# M-S_rev_01.net
KiCad netlist of a schematic drawn in EAGLE
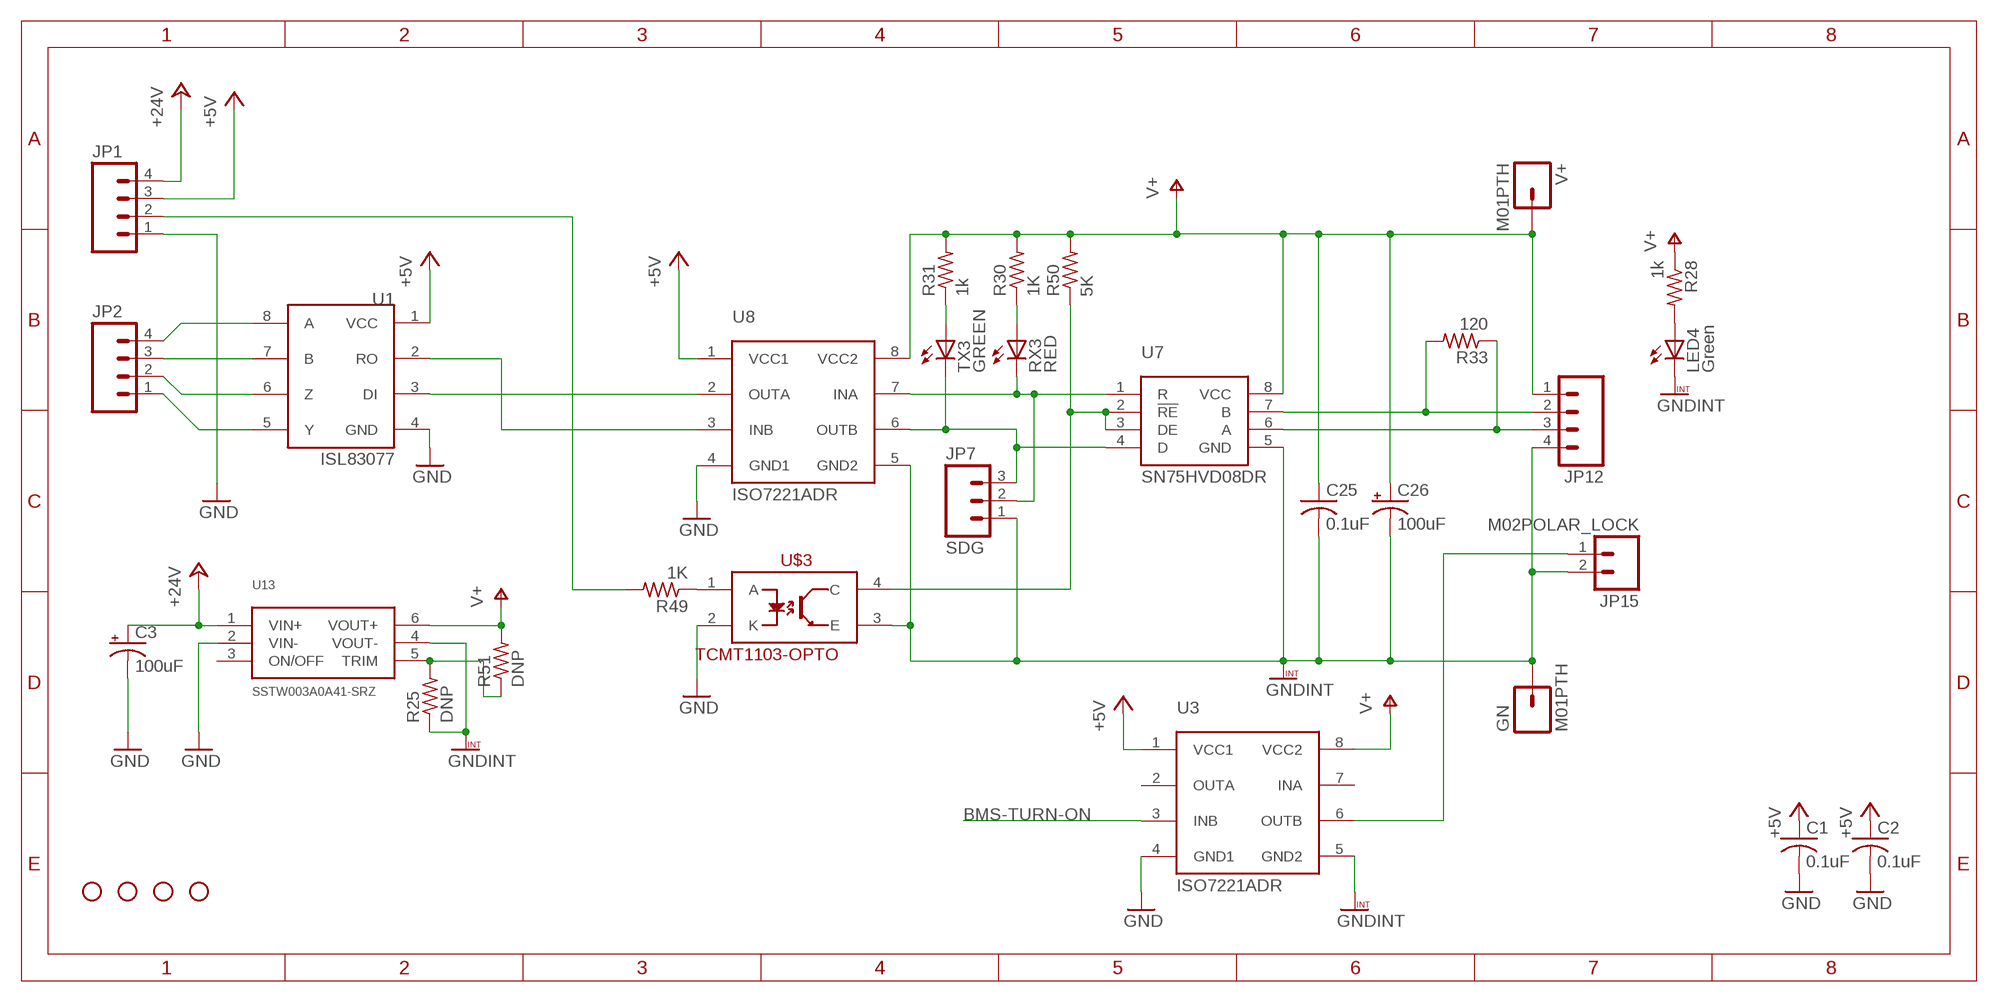
[diagram p0: schematic, sheet 1]
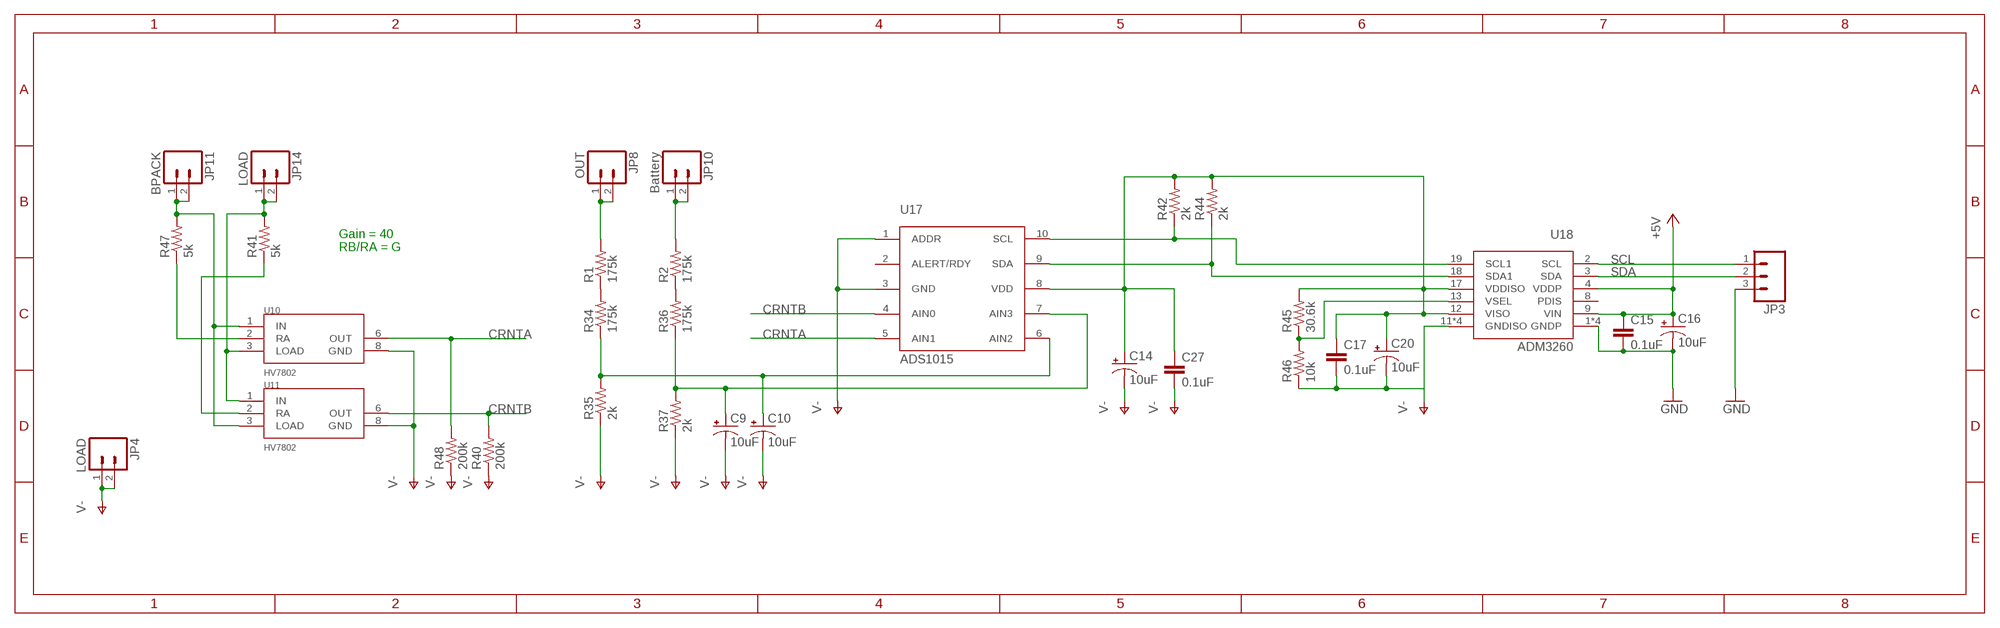
[diagram p1: schematic, sheet 2]
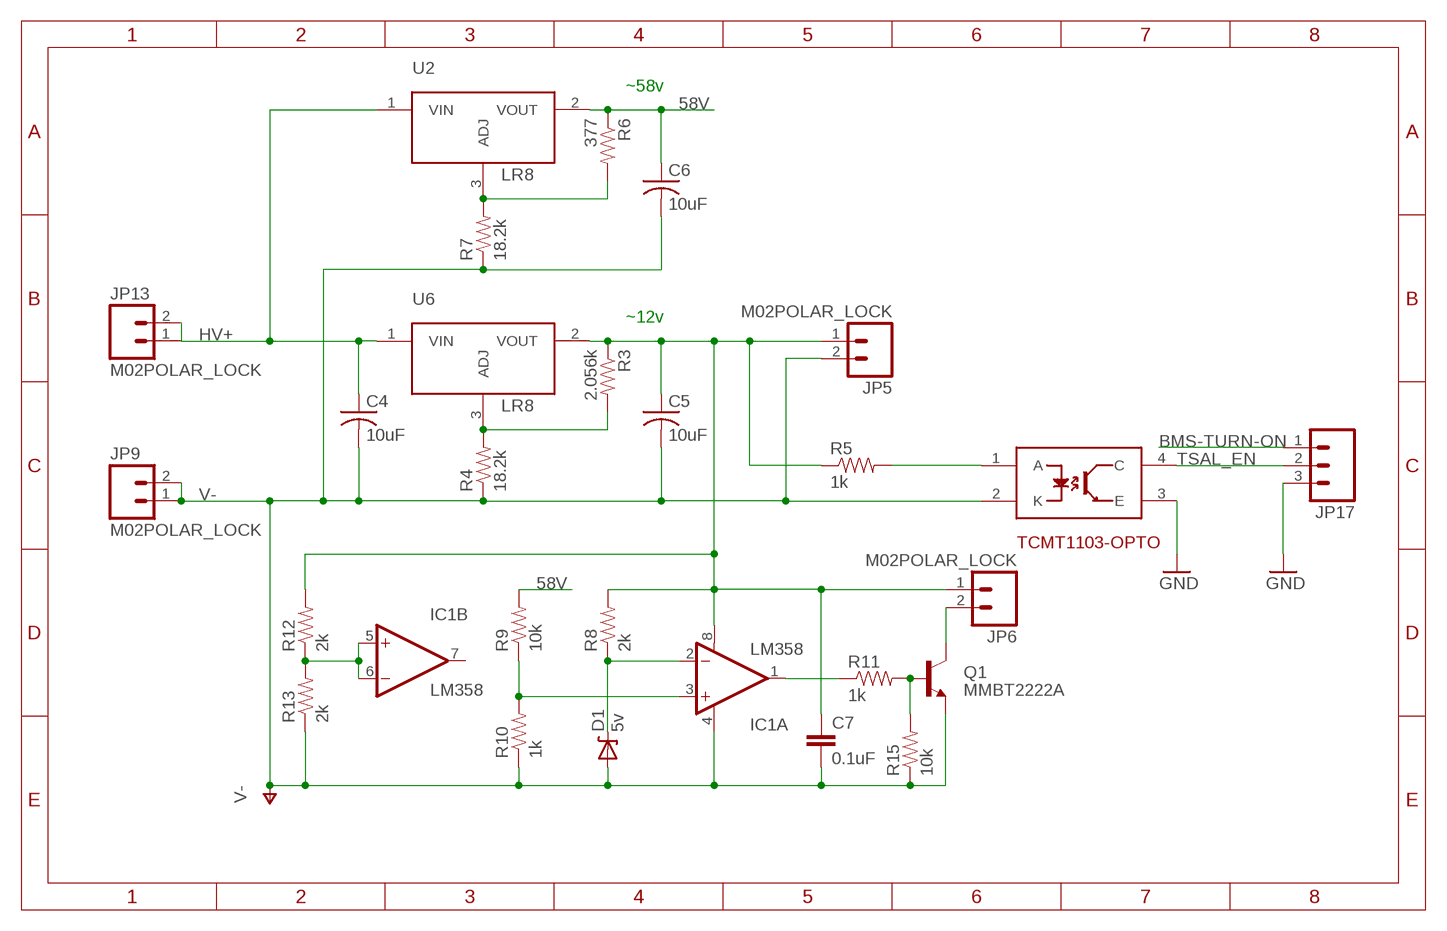
[diagram p2: schematic, sheet 3]

(export (version "E")
  (design (tool "Eeschema 10.0.6"))
  (components
    (comp (ref "C4")
      (value "10uF")
      (footprint "eagle-import:C050-030X075")
      (libsource (lib "eagle-import") (part "C-US050-030X075"))
    )
    (comp (ref "C5")
      (value "10uF")
      (footprint "eagle-import:C0805")
      (libsource (lib "eagle-import") (part "C-USC0805"))
    )
    (comp (ref "C6")
      (value "10uF")
      (footprint "eagle-import:C0805")
      (libsource (lib "eagle-import") (part "C-USC0805"))
    )
    (comp (ref "C7")
      (value "0.1uF")
      (footprint "eagle-import:0805")
      (libsource (lib "eagle-import") (part "SparkFun-Passives_CAP0805"))
    )
    (comp (ref "D1")
      (value "5v")
      (footprint "eagle-import:SOD-323@1")
      (libsource (lib "eagle-import") (part "DIODE-ZENER-BZT52"))
    )
    (comp (ref "IC1")
      (value "LM358")
      (footprint "eagle-import:SO08")
      (libsource (lib "eagle-import") (part "OPAMP-DUALU"))
    )
    (comp (ref "JP5")
      (value "M02POLAR_LOCK")
      (footprint "eagle-import:MOLEX-1X2_LOCK")
      (libsource (lib "eagle-import") (part "M02POLAR_LOCK"))
    )
    (comp (ref "JP6")
      (value "M02POLAR_LOCK")
      (footprint "eagle-import:MOLEX-1X2_LOCK")
      (libsource (lib "eagle-import") (part "M02POLAR_LOCK"))
    )
    (comp (ref "JP9")
      (value "M02POLAR_LOCK")
      (footprint "eagle-import:MOLEX-1X2_LOCK")
      (libsource (lib "eagle-import") (part "M02POLAR_LOCK"))
    )
    (comp (ref "JP13")
      (value "M02POLAR_LOCK")
      (footprint "eagle-import:MOLEX-1X2_LOCK")
      (libsource (lib "eagle-import") (part "M02POLAR_LOCK"))
    )
    (comp (ref "JP17")
      (value "M03POLAR_LOCK")
      (footprint "eagle-import:MOLEX-1X3_LOCK")
      (libsource (lib "eagle-import") (part "M03POLAR_LOCK"))
    )
    (comp (ref "Q1")
      (value "MMBT2222A")
      (footprint "eagle-import:SOT23")
      (libsource (lib "eagle-import") (part "TRANSISTOR_NPNMMBT2222A"))
    )
    (comp (ref "R3")
      (value "2.056k")
      (footprint "eagle-import:0805")
      (libsource (lib "eagle-import") (part "RESISTOR0805-RES"))
    )
    (comp (ref "R4")
      (value "18.2k")
      (footprint "eagle-import:0805")
      (libsource (lib "eagle-import") (part "RESISTOR0805-RES"))
    )
    (comp (ref "R5")
      (value "1k")
      (footprint "eagle-import:0805")
      (libsource (lib "eagle-import") (part "RESISTOR0805-RES"))
    )
    (comp (ref "R6")
      (value "377")
      (footprint "eagle-import:0805")
      (libsource (lib "eagle-import") (part "RESISTOR0805-RES"))
    )
    (comp (ref "R7")
      (value "18.2k")
      (footprint "eagle-import:0805")
      (libsource (lib "eagle-import") (part "RESISTOR0805-RES"))
    )
    (comp (ref "R8")
      (value "2k")
      (footprint "eagle-import:0805")
      (libsource (lib "eagle-import") (part "RESISTOR0805-RES"))
    )
    (comp (ref "R9")
      (value "10k")
      (footprint "eagle-import:0805")
      (libsource (lib "eagle-import") (part "RESISTOR0805-RES"))
    )
    (comp (ref "R10")
      (value "1k")
      (footprint "eagle-import:0805")
      (libsource (lib "eagle-import") (part "RESISTOR0805-RES"))
    )
    (comp (ref "R11")
      (value "1k")
      (footprint "eagle-import:0805")
      (libsource (lib "eagle-import") (part "RESISTOR0805-RES"))
    )
    (comp (ref "R12")
      (value "2k")
      (footprint "eagle-import:0805")
      (libsource (lib "eagle-import") (part "RESISTOR0805-RES"))
    )
    (comp (ref "R13")
      (value "2k")
      (footprint "eagle-import:0805")
      (libsource (lib "eagle-import") (part "RESISTOR0805-RES"))
    )
    (comp (ref "R15")
      (value "10k")
      (footprint "eagle-import:0805")
      (libsource (lib "eagle-import") (part "RESISTOR0805-RES"))
    )
    (comp (ref "U$11")
      (value "TCMT1103-OPTO")
      (footprint "eagle-import:SSOP-4")
      (libsource (lib "eagle-import") (part "TCMT1103-OPTO"))
    )
    (comp (ref "U2")
      (value "LR8")
      (footprint "eagle-import:DPAK")
      (libsource (lib "eagle-import") (part "LR8"))
    )
    (comp (ref "U6")
      (value "LR8")
      (footprint "eagle-import:DPAK")
      (libsource (lib "eagle-import") (part "LR8"))
    )
    (comp (ref "C9")
      (value "10uF")
      (footprint "eagle-import:EIA3216")
      (libsource (lib "eagle-import") (part "CAP_POL1206"))
    )
    (comp (ref "C10")
      (value "10uF")
      (footprint "eagle-import:EIA3216")
      (libsource (lib "eagle-import") (part "CAP_POL1206"))
    )
    (comp (ref "C14")
      (value "10uF")
      (footprint "eagle-import:EIA3216")
      (libsource (lib "eagle-import") (part "CAP_POL1206"))
    )
    (comp (ref "C15")
      (value "0.1uF")
      (footprint "eagle-import:0805")
      (libsource (lib "eagle-import") (part "CAP0805"))
    )
    (comp (ref "C16")
      (value "10uF")
      (footprint "eagle-import:EIA3216")
      (libsource (lib "eagle-import") (part "CAP_POL1206"))
    )
    (comp (ref "C17")
      (value "0.1uF")
      (footprint "eagle-import:0805")
      (libsource (lib "eagle-import") (part "CAP0805"))
    )
    (comp (ref "C20")
      (value "10uF")
      (footprint "eagle-import:EIA3216")
      (libsource (lib "eagle-import") (part "CAP_POL1206"))
    )
    (comp (ref "C27")
      (value "0.1uF")
      (footprint "eagle-import:0805")
      (libsource (lib "eagle-import") (part "CAP0805"))
    )
    (comp (ref "JP3")
      (value "M03POLAR_LOCK")
      (footprint "eagle-import:MOLEX-1X3_LOCK")
      (libsource (lib "eagle-import") (part "M03POLAR_LOCK"))
    )
    (comp (ref "JP4")
      (value "LOAD")
      (footprint "eagle-import:MOLEX-1X2_LOCK")
      (libsource (lib "eagle-import") (part "M02POLAR_LOCK"))
    )
    (comp (ref "JP8")
      (value "OUT")
      (footprint "eagle-import:MOLEX-1X2_LOCK")
      (libsource (lib "eagle-import") (part "M02POLAR_LOCK"))
    )
    (comp (ref "JP10")
      (value "Battery")
      (footprint "eagle-import:MOLEX-1X2_LOCK")
      (libsource (lib "eagle-import") (part "M02POLAR_LOCK"))
    )
    (comp (ref "JP11")
      (value "BPACK")
      (footprint "eagle-import:MOLEX-1X2_LOCK")
      (libsource (lib "eagle-import") (part "M02POLAR_LOCK"))
    )
    (comp (ref "JP14")
      (value "LOAD")
      (footprint "eagle-import:MOLEX-1X2_LOCK")
      (libsource (lib "eagle-import") (part "M02POLAR_LOCK"))
    )
    (comp (ref "R1")
      (value "175k")
      (footprint "eagle-import:1206")
      (libsource (lib "eagle-import") (part "RESISTOR1206"))
    )
    (comp (ref "R2")
      (value "175k")
      (footprint "eagle-import:1206")
      (libsource (lib "eagle-import") (part "RESISTOR1206"))
    )
    (comp (ref "R34")
      (value "175k")
      (footprint "eagle-import:1206")
      (libsource (lib "eagle-import") (part "RESISTOR1206"))
    )
    (comp (ref "R35")
      (value "2k")
      (footprint "eagle-import:1206")
      (libsource (lib "eagle-import") (part "RESISTOR1206"))
    )
    (comp (ref "R36")
      (value "175k")
      (footprint "eagle-import:1206")
      (libsource (lib "eagle-import") (part "RESISTOR1206"))
    )
    (comp (ref "R37")
      (value "2k")
      (footprint "eagle-import:1206")
      (libsource (lib "eagle-import") (part "RESISTOR1206"))
    )
    (comp (ref "R40")
      (value "200k")
      (footprint "eagle-import:0805")
      (libsource (lib "eagle-import") (part "RESISTOR0805-RES"))
    )
    (comp (ref "R41")
      (value "5k")
      (footprint "eagle-import:0805")
      (libsource (lib "eagle-import") (part "RESISTOR0805-RES"))
    )
    (comp (ref "R42")
      (value "2k")
      (footprint "eagle-import:0805")
      (libsource (lib "eagle-import") (part "RESISTOR0805-RES"))
    )
    (comp (ref "R44")
      (value "2k")
      (footprint "eagle-import:0805")
      (libsource (lib "eagle-import") (part "RESISTOR0805-RES"))
    )
    (comp (ref "R45")
      (value "30.6k")
      (footprint "eagle-import:0805")
      (libsource (lib "eagle-import") (part "RESISTOR0805-RES"))
    )
    (comp (ref "R46")
      (value "10k")
      (footprint "eagle-import:0805")
      (libsource (lib "eagle-import") (part "RESISTOR0805-RES"))
    )
    (comp (ref "R47")
      (value "5k")
      (footprint "eagle-import:0805")
      (libsource (lib "eagle-import") (part "RESISTOR0805-RES"))
    )
    (comp (ref "R48")
      (value "200k")
      (footprint "eagle-import:0805")
      (libsource (lib "eagle-import") (part "RESISTOR0805-RES"))
    )
    (comp (ref "U10")
      (value "HV7802")
      (footprint "eagle-import:MSOP-8")
      (libsource (lib "eagle-import") (part "HV7802"))
    )
    (comp (ref "U11")
      (value "HV7802")
      (footprint "eagle-import:MSOP-8")
      (libsource (lib "eagle-import") (part "HV7802"))
    )
    (comp (ref "U17")
      (value "ADS1015")
      (footprint "eagle-import:MSOP-10")
      (libsource (lib "eagle-import") (part "ADS1015"))
    )
    (comp (ref "U18")
      (value "ADM3260")
      (footprint "eagle-import:SSOP-20")
      (libsource (lib "eagle-import") (part "ADM3260"))
    )
    (comp (ref "C1")
      (value "0.1uF")
      (footprint "eagle-import:C0805")
      (libsource (lib "eagle-import") (part "C-USC0805"))
    )
    (comp (ref "C2")
      (value "0.1uF")
      (footprint "eagle-import:C0805")
      (libsource (lib "eagle-import") (part "C-USC0805"))
    )
    (comp (ref "C3")
      (value "100uF")
      (footprint "eagle-import:C_6032-28W")
      (libsource (lib "eagle-import") (part "CPOL-USC/6032-28W"))
    )
    (comp (ref "C25")
      (value "0.1uF")
      (footprint "eagle-import:C0805")
      (libsource (lib "eagle-import") (part "C-USC0805"))
    )
    (comp (ref "C26")
      (value "100uF")
      (footprint "eagle-import:C_6032-28W")
      (libsource (lib "eagle-import") (part "CPOL-USC/6032-28W"))
    )
    (comp (ref "GN")
      (value "M01PTH")
      (footprint "eagle-import:1X01")
      (libsource (lib "eagle-import") (part "M01PTH"))
    )
    (comp (ref "JP1")
      (value "M04POLAR_LOCK")
      (footprint "eagle-import:MOLEX-1X4_LOCK")
      (libsource (lib "eagle-import") (part "M04POLAR_LOCK"))
    )
    (comp (ref "JP2")
      (value "M04POLAR_LOCK")
      (footprint "eagle-import:MOLEX-1X4_LOCK")
      (libsource (lib "eagle-import") (part "M04POLAR_LOCK"))
    )
    (comp (ref "JP7")
      (value "SDG")
      (footprint "eagle-import:1X03_LOCK_LONGPADS")
      (libsource (lib "eagle-import") (part "M03LOCK_LONGPADS"))
    )
    (comp (ref "JP12")
      (value "M04POLAR_LOCK")
      (footprint "eagle-import:MOLEX-1X4_LOCK")
      (libsource (lib "eagle-import") (part "M04POLAR_LOCK"))
    )
    (comp (ref "JP15")
      (value "M02POLAR_LOCK")
      (footprint "eagle-import:MOLEX-1X2_LOCK")
      (libsource (lib "eagle-import") (part "M02POLAR_LOCK"))
    )
    (comp (ref "LED4")
      (value "Green")
      (footprint "eagle-import:CHIPLED_0805")
      (libsource (lib "eagle-import") (part "LEDCHIPLED_0805"))
    )
    (comp (ref "R25")
      (value "DNP")
      (footprint "eagle-import:R0805")
      (libsource (lib "eagle-import") (part "R-US_R0805"))
    )
    (comp (ref "R28")
      (value "1k")
      (footprint "eagle-import:R0805")
      (libsource (lib "eagle-import") (part "R-US_R0805"))
    )
    (comp (ref "R30")
      (value "1K")
      (footprint "eagle-import:R0805")
      (libsource (lib "eagle-import") (part "R-US_R0805"))
    )
    (comp (ref "R31")
      (value "1k")
      (footprint "eagle-import:R0805")
      (libsource (lib "eagle-import") (part "R-US_R0805"))
    )
    (comp (ref "R33")
      (value "120")
      (footprint "eagle-import:R0805")
      (libsource (lib "eagle-import") (part "R-US_R0805"))
    )
    (comp (ref "R49")
      (value "1K")
      (footprint "eagle-import:R0805")
      (libsource (lib "eagle-import") (part "R-US_R0805"))
    )
    (comp (ref "R50")
      (value "5K")
      (footprint "eagle-import:R0805")
      (libsource (lib "eagle-import") (part "R-US_R0805"))
    )
    (comp (ref "R51")
      (value "DNP")
      (footprint "eagle-import:R0805")
      (libsource (lib "eagle-import") (part "R-US_R0805"))
    )
    (comp (ref "RX3")
      (value "RED")
      (footprint "eagle-import:CHIPLED_0805")
      (libsource (lib "eagle-import") (part "LEDCHIPLED_0805"))
    )
    (comp (ref "STANDOFF1")
      (value "STAND-OFF")
      (footprint "eagle-import:STAND-OFF")
      (libsource (lib "eagle-import") (part "STAND-OFF"))
    )
    (comp (ref "STANDOFF2")
      (value "STAND-OFF")
      (footprint "eagle-import:STAND-OFF")
      (libsource (lib "eagle-import") (part "STAND-OFF"))
    )
    (comp (ref "STANDOFF3")
      (value "STAND-OFF")
      (footprint "eagle-import:STAND-OFF")
      (libsource (lib "eagle-import") (part "STAND-OFF"))
    )
    (comp (ref "STANDOFF4")
      (value "STAND-OFF")
      (footprint "eagle-import:STAND-OFF")
      (libsource (lib "eagle-import") (part "STAND-OFF"))
    )
    (comp (ref "TX3")
      (value "GREEN")
      (footprint "eagle-import:CHIPLED_0805")
      (libsource (lib "eagle-import") (part "LEDCHIPLED_0805"))
    )
    (comp (ref "U$3")
      (value "TCMT1103-OPTO")
      (footprint "eagle-import:SSOP-4")
      (libsource (lib "eagle-import") (part "TCMT1103-OPTO"))
    )
    (comp (ref "U1")
      (value "ISL83077")
      (footprint "eagle-import:SO08")
      (libsource (lib "eagle-import") (part "ISL83077"))
    )
    (comp (ref "U3")
      (value "ISO7221ADR")
      (footprint "eagle-import:SOIC-8")
      (libsource (lib "eagle-import") (part "ISO7221ADR"))
    )
    (comp (ref "U7")
      (value "SN75HVD08DR")
      (footprint "eagle-import:SO-8")
      (libsource (lib "eagle-import") (part "SN75HVD08DR"))
    )
    (comp (ref "U8")
      (value "ISO7221ADR")
      (footprint "eagle-import:SOIC-8")
      (libsource (lib "eagle-import") (part "ISO7221ADR"))
    )
    (comp (ref "U13")
      (value "SSTW003A0A41-SRZ")
      (footprint "eagle-import:SSTW003A0A41-SRZ")
      (libsource (lib "eagle-import") (part "SSTW003A0A41-SRZ"))
    )
    (comp (ref "V+")
      (value "M01PTH")
      (footprint "eagle-import:1X01")
      (libsource (lib "eagle-import") (part "M01PTH"))
    )
  )
  (nets
    (net (code "1") (name "+5V") (class "Default")
      (node (ref "C1") (pin "1") (pinfunction "1_1") (pintype "passive"))
      (node (ref "C15") (pin "1") (pinfunction "1_1") (pintype "passive"))
      (node (ref "C16") (pin "A") (pinfunction "+_A") (pintype "passive"))
      (node (ref "C2") (pin "1") (pinfunction "1_1") (pintype "passive"))
      (node (ref "JP1") (pin "3") (pinfunction "3_3") (pintype "passive"))
      (node (ref "U1") (pin "1") (pinfunction "VCC_1") (pintype "bidirectional"))
      (node (ref "U18") (pin "4") (pinfunction "VDDP_4") (pintype "bidirectional"))
      (node (ref "U18") (pin "9") (pinfunction "VIN_9") (pintype "bidirectional"))
      (node (ref "U3") (pin "1") (pinfunction "VCC1_1") (pintype "bidirectional"))
      (node (ref "U8") (pin "1") (pinfunction "VCC1_1") (pintype "bidirectional"))
    )
    (net (code "2") (name "+24V") (class "Default")
      (node (ref "C3") (pin "+") (pinfunction "+_+") (pintype "passive"))
      (node (ref "JP1") (pin "4") (pinfunction "4_4") (pintype "passive"))
      (node (ref "U13") (pin "1") (pinfunction "VIN+_1") (pintype "bidirectional"))
    )
    (net (code "3") (name "58V") (class "Default")
      (node (ref "C6") (pin "1") (pinfunction "1_1") (pintype "passive"))
      (node (ref "R6") (pin "1") (pinfunction "1_1") (pintype "passive"))
      (node (ref "R9") (pin "2") (pinfunction "2_2") (pintype "passive"))
      (node (ref "U2") (pin "2") (pinfunction "VOUT_2") (pintype "bidirectional"))
    )
    (net (code "4") (name "BMS-TURN-ON") (class "Default")
      (node (ref "JP17") (pin "1") (pinfunction "1_1") (pintype "passive"))
      (node (ref "U3") (pin "3") (pinfunction "INB_3") (pintype "bidirectional"))
    )
    (net (code "5") (name "CRNTA") (class "Default")
      (node (ref "R48") (pin "2") (pinfunction "2_2") (pintype "passive"))
      (node (ref "U10") (pin "6") (pinfunction "OUT_6") (pintype "bidirectional"))
      (node (ref "U17") (pin "5") (pinfunction "AIN1_5") (pintype "bidirectional"))
    )
    (net (code "6") (name "CRNTB") (class "Default")
      (node (ref "R40") (pin "2") (pinfunction "2_2") (pintype "passive"))
      (node (ref "U11") (pin "6") (pinfunction "OUT_6") (pintype "bidirectional"))
      (node (ref "U17") (pin "4") (pinfunction "AIN0_4") (pintype "bidirectional"))
    )
    (net (code "7") (name "GND") (class "Default")
      (node (ref "C1") (pin "2") (pinfunction "2_2") (pintype "passive"))
      (node (ref "C15") (pin "2") (pinfunction "2_2") (pintype "passive"))
      (node (ref "C16") (pin "C") (pinfunction "-_C") (pintype "passive"))
      (node (ref "C2") (pin "2") (pinfunction "2_2") (pintype "passive"))
      (node (ref "C3") (pin "-") (pinfunction "-_-") (pintype "passive"))
      (node (ref "JP1") (pin "1") (pinfunction "1_1") (pintype "passive"))
      (node (ref "JP17") (pin "3") (pinfunction "3_3") (pintype "passive"))
      (node (ref "JP3") (pin "3") (pinfunction "3_3") (pintype "passive"))
      (node (ref "U$11") (pin "3") (pinfunction "E_3") (pintype "bidirectional"))
      (node (ref "U$3") (pin "2") (pinfunction "K_2") (pintype "bidirectional"))
      (node (ref "U1") (pin "4") (pinfunction "GND_4") (pintype "bidirectional"))
      (node (ref "U13") (pin "2") (pinfunction "VIN-_2") (pintype "bidirectional"))
      (node (ref "U18") (pin "1") (pinfunction "GNDP_1") (pintype "bidirectional"))
      (node (ref "U18") (pin "10") (pinfunction "GNDP_10") (pintype "bidirectional"))
      (node (ref "U18") (pin "5") (pinfunction "GNDP_5") (pintype "bidirectional"))
      (node (ref "U18") (pin "7") (pinfunction "GNDP_7") (pintype "bidirectional"))
      (node (ref "U3") (pin "4") (pinfunction "GND1_4") (pintype "bidirectional"))
      (node (ref "U8") (pin "4") (pinfunction "GND1_4") (pintype "bidirectional"))
    )
    (net (code "8") (name "GNDINT") (class "Default")
      (node (ref "C25") (pin "2") (pinfunction "2_2") (pintype "passive"))
      (node (ref "C26") (pin "-") (pinfunction "-_-") (pintype "passive"))
      (node (ref "GN") (pin "1") (pinfunction "1_1") (pintype "passive"))
      (node (ref "JP12") (pin "4") (pinfunction "4_4") (pintype "passive"))
      (node (ref "JP15") (pin "2") (pinfunction "2_2") (pintype "passive"))
      (node (ref "JP7") (pin "1") (pinfunction "1_1") (pintype "passive"))
      (node (ref "LED4") (pin "C") (pinfunction "C_C") (pintype "passive"))
      (node (ref "R25") (pin "1") (pinfunction "1_1") (pintype "passive"))
      (node (ref "U$3") (pin "3") (pinfunction "E_3") (pintype "bidirectional"))
      (node (ref "U13") (pin "4") (pinfunction "VOUT-_4") (pintype "bidirectional"))
      (node (ref "U3") (pin "5") (pinfunction "GND2_5") (pintype "bidirectional"))
      (node (ref "U7") (pin "5") (pinfunction "GND_5") (pintype "bidirectional"))
      (node (ref "U8") (pin "5") (pinfunction "GND2_5") (pintype "bidirectional"))
    )
    (net (code "9") (name "HV+") (class "Default")
      (node (ref "C4") (pin "1") (pinfunction "1_1") (pintype "passive"))
      (node (ref "JP13") (pin "1") (pinfunction "1_1") (pintype "passive"))
      (node (ref "JP13") (pin "2") (pinfunction "2_2") (pintype "passive"))
      (node (ref "U2") (pin "1") (pinfunction "VIN_1") (pintype "bidirectional"))
      (node (ref "U6") (pin "1") (pinfunction "VIN_1") (pintype "bidirectional"))
    )
    (net (code "10") (name "Net-(C9-+)") (class "Default")
      (node (ref "C9") (pin "A") (pinfunction "+_A") (pintype "passive"))
      (node (ref "R36") (pin "1") (pinfunction "1_1") (pintype "passive"))
      (node (ref "R37") (pin "2") (pinfunction "2_2") (pintype "passive"))
      (node (ref "U17") (pin "7") (pinfunction "AIN3_7") (pintype "bidirectional"))
    )
    (net (code "11") (name "Net-(C10-+)") (class "Default")
      (node (ref "C10") (pin "A") (pinfunction "+_A") (pintype "passive"))
      (node (ref "R34") (pin "1") (pinfunction "1_1") (pintype "passive"))
      (node (ref "R35") (pin "2") (pinfunction "2_2") (pintype "passive"))
      (node (ref "U17") (pin "6") (pinfunction "AIN2_6") (pintype "bidirectional"))
    )
    (net (code "12") (name "Net-(C14-+)") (class "Default")
      (node (ref "C14") (pin "A") (pinfunction "+_A") (pintype "passive"))
      (node (ref "C17") (pin "1") (pinfunction "1_1") (pintype "passive"))
      (node (ref "C20") (pin "A") (pinfunction "+_A") (pintype "passive"))
      (node (ref "C27") (pin "1") (pinfunction "1_1") (pintype "passive"))
      (node (ref "R42") (pin "2") (pinfunction "2_2") (pintype "passive"))
      (node (ref "R44") (pin "2") (pinfunction "2_2") (pintype "passive"))
      (node (ref "R45") (pin "2") (pinfunction "2_2") (pintype "passive"))
      (node (ref "U17") (pin "8") (pinfunction "VDD_8") (pintype "bidirectional"))
      (node (ref "U18") (pin "12") (pinfunction "VISO_12") (pintype "bidirectional"))
      (node (ref "U18") (pin "17") (pinfunction "VDDISO_17") (pintype "bidirectional"))
    )
    (net (code "13") (name "Net-(D1-C)") (class "Default")
      (node (ref "D1") (pin "1") (pinfunction "C_1") (pintype "passive"))
      (node (ref "IC1") (pin "2") (pinfunction "-IN_2") (pintype "input"))
      (node (ref "R8") (pin "1") (pinfunction "1_1") (pintype "passive"))
    )
    (net (code "14") (name "Net-(IC1A-+IN)") (class "Default")
      (node (ref "IC1") (pin "3") (pinfunction "+IN_3") (pintype "input"))
      (node (ref "R10") (pin "2") (pinfunction "2_2") (pintype "passive"))
      (node (ref "R9") (pin "1") (pinfunction "1_1") (pintype "passive"))
    )
    (net (code "15") (name "Net-(IC1A-OUT)") (class "Default")
      (node (ref "IC1") (pin "1") (pinfunction "OUT_1") (pintype "output"))
      (node (ref "R11") (pin "1") (pinfunction "1_1") (pintype "passive"))
    )
    (net (code "16") (name "Net-(IC1A-V+)") (class "Default")
      (node (ref "C5") (pin "1") (pinfunction "1_1") (pintype "passive"))
      (node (ref "C7") (pin "1") (pinfunction "1_1") (pintype "passive"))
      (node (ref "IC1") (pin "8") (pinfunction "V+_8") (pintype "power_in"))
      (node (ref "JP5") (pin "1") (pinfunction "1_1") (pintype "passive"))
      (node (ref "JP6") (pin "1") (pinfunction "1_1") (pintype "passive"))
      (node (ref "R12") (pin "2") (pinfunction "2_2") (pintype "passive"))
      (node (ref "R3") (pin "1") (pinfunction "1_1") (pintype "passive"))
      (node (ref "R5") (pin "1") (pinfunction "1_1") (pintype "passive"))
      (node (ref "R8") (pin "2") (pinfunction "2_2") (pintype "passive"))
      (node (ref "U6") (pin "2") (pinfunction "VOUT_2") (pintype "bidirectional"))
    )
    (net (code "17") (name "Net-(IC1B-+IN)") (class "Default")
      (node (ref "IC1") (pin "5") (pinfunction "+IN_5") (pintype "input"))
      (node (ref "IC1") (pin "6") (pinfunction "-IN_6") (pintype "input"))
      (node (ref "R12") (pin "1") (pinfunction "1_1") (pintype "passive"))
      (node (ref "R13") (pin "2") (pinfunction "2_2") (pintype "passive"))
    )
    (net (code "18") (name "Net-(JP1-Pad2)") (class "Default")
      (node (ref "JP1") (pin "2") (pinfunction "2_2") (pintype "passive"))
      (node (ref "R49") (pin "2") (pinfunction "2_2") (pintype "passive"))
    )
    (net (code "19") (name "Net-(JP8-Pad1)") (class "Default")
      (node (ref "JP8") (pin "1") (pinfunction "1_1") (pintype "passive"))
      (node (ref "JP8") (pin "2") (pinfunction "2_2") (pintype "passive"))
      (node (ref "R1") (pin "2") (pinfunction "2_2") (pintype "passive"))
    )
    (net (code "20") (name "Net-(JP10-Pad1)") (class "Default")
      (node (ref "JP10") (pin "1") (pinfunction "1_1") (pintype "passive"))
      (node (ref "JP10") (pin "2") (pinfunction "2_2") (pintype "passive"))
      (node (ref "R2") (pin "2") (pinfunction "2_2") (pintype "passive"))
    )
    (net (code "21") (name "Net-(LED4-PadA)") (class "Default")
      (node (ref "LED4") (pin "A") (pinfunction "A_A") (pintype "passive"))
      (node (ref "R28") (pin "2") (pinfunction "2_2") (pintype "passive"))
    )
    (net (code "22") (name "Net-(Q1-B)") (class "Default")
      (node (ref "Q1") (pin "1") (pinfunction "B_1") (pintype "passive"))
      (node (ref "R11") (pin "2") (pinfunction "2_2") (pintype "passive"))
      (node (ref "R15") (pin "2") (pinfunction "2_2") (pintype "passive"))
    )
    (net (code "23") (name "Net-(Q1-C)") (class "Default")
      (node (ref "JP6") (pin "2") (pinfunction "2_2") (pintype "passive"))
      (node (ref "Q1") (pin "3") (pinfunction "C_3") (pintype "passive"))
    )
    (net (code "24") (name "Net-(R1-Pad1)") (class "Default")
      (node (ref "R1") (pin "1") (pinfunction "1_1") (pintype "passive"))
      (node (ref "R34") (pin "2") (pinfunction "2_2") (pintype "passive"))
    )
    (net (code "25") (name "Net-(R2-Pad1)") (class "Default")
      (node (ref "R2") (pin "1") (pinfunction "1_1") (pintype "passive"))
      (node (ref "R36") (pin "2") (pinfunction "2_2") (pintype "passive"))
    )
    (net (code "26") (name "Net-(R30-Pad1)") (class "Default")
      (node (ref "R30") (pin "1") (pinfunction "1_1") (pintype "passive"))
      (node (ref "RX3") (pin "A") (pinfunction "A_A") (pintype "passive"))
    )
    (net (code "27") (name "Net-(R31-Pad1)") (class "Default")
      (node (ref "R31") (pin "1") (pinfunction "1_1") (pintype "passive"))
      (node (ref "TX3") (pin "A") (pinfunction "A_A") (pintype "passive"))
    )
    (net (code "28") (name "Net-(U$3-A)") (class "Default")
      (node (ref "R49") (pin "1") (pinfunction "1_1") (pintype "passive"))
      (node (ref "U$3") (pin "1") (pinfunction "A_1") (pintype "bidirectional"))
    )
    (net (code "29") (name "Net-(U$3-C)") (class "Default")
      (node (ref "R50") (pin "1") (pinfunction "1_1") (pintype "passive"))
      (node (ref "U$3") (pin "4") (pinfunction "C_4") (pintype "bidirectional"))
      (node (ref "U7") (pin "2") (pinfunction "~{RE}_2") (pintype "bidirectional"))
      (node (ref "U7") (pin "3") (pinfunction "DE_3") (pintype "bidirectional"))
    )
    (net (code "30") (name "Net-(U$11-A)") (class "Default")
      (node (ref "R5") (pin "2") (pinfunction "2_2") (pintype "passive"))
      (node (ref "U$11") (pin "1") (pinfunction "A_1") (pintype "bidirectional"))
    )
    (net (code "31") (name "Net-(U1-A)") (class "Default")
      (node (ref "JP2") (pin "4") (pinfunction "4_4") (pintype "passive"))
      (node (ref "U1") (pin "8") (pinfunction "A_8") (pintype "bidirectional"))
    )
    (net (code "32") (name "Net-(U1-B)") (class "Default")
      (node (ref "JP2") (pin "3") (pinfunction "3_3") (pintype "passive"))
      (node (ref "U1") (pin "7") (pinfunction "B_7") (pintype "bidirectional"))
    )
    (net (code "33") (name "Net-(U1-DI)") (class "Default")
      (node (ref "U1") (pin "3") (pinfunction "DI_3") (pintype "bidirectional"))
      (node (ref "U8") (pin "2") (pinfunction "OUTA_2") (pintype "bidirectional"))
    )
    (net (code "34") (name "Net-(U1-RO)") (class "Default")
      (node (ref "U1") (pin "2") (pinfunction "RO_2") (pintype "bidirectional"))
      (node (ref "U8") (pin "3") (pinfunction "INB_3") (pintype "bidirectional"))
    )
    (net (code "35") (name "Net-(U1-Y)") (class "Default")
      (node (ref "JP2") (pin "1") (pinfunction "1_1") (pintype "passive"))
      (node (ref "U1") (pin "5") (pinfunction "Y_5") (pintype "bidirectional"))
    )
    (net (code "36") (name "Net-(U1-Z)") (class "Default")
      (node (ref "JP2") (pin "2") (pinfunction "2_2") (pintype "passive"))
      (node (ref "U1") (pin "6") (pinfunction "Z_6") (pintype "bidirectional"))
    )
    (net (code "37") (name "Net-(U2-ADJ)") (class "Default")
      (node (ref "R6") (pin "2") (pinfunction "2_2") (pintype "passive"))
      (node (ref "R7") (pin "2") (pinfunction "2_2") (pintype "passive"))
      (node (ref "U2") (pin "3") (pinfunction "ADJ_3") (pintype "bidirectional"))
    )
    (net (code "38") (name "Net-(U3-OUTB)") (class "Default")
      (node (ref "JP15") (pin "1") (pinfunction "1_1") (pintype "passive"))
      (node (ref "U3") (pin "6") (pinfunction "OUTB_6") (pintype "bidirectional"))
    )
    (net (code "39") (name "Net-(U6-ADJ)") (class "Default")
      (node (ref "R3") (pin "2") (pinfunction "2_2") (pintype "passive"))
      (node (ref "R4") (pin "2") (pinfunction "2_2") (pintype "passive"))
      (node (ref "U6") (pin "3") (pinfunction "ADJ_3") (pintype "bidirectional"))
    )
    (net (code "40") (name "Net-(U7-A)") (class "Default")
      (node (ref "JP12") (pin "3") (pinfunction "3_3") (pintype "passive"))
      (node (ref "R33") (pin "1") (pinfunction "1_1") (pintype "passive"))
      (node (ref "U7") (pin "6") (pinfunction "A_6") (pintype "bidirectional"))
    )
    (net (code "41") (name "Net-(U7-B)") (class "Default")
      (node (ref "JP12") (pin "2") (pinfunction "2_2") (pintype "passive"))
      (node (ref "R33") (pin "2") (pinfunction "2_2") (pintype "passive"))
      (node (ref "U7") (pin "7") (pinfunction "B_7") (pintype "bidirectional"))
    )
    (net (code "42") (name "Net-(U7-D)") (class "Default")
      (node (ref "JP7") (pin "3") (pinfunction "3_3") (pintype "passive"))
      (node (ref "TX3") (pin "C") (pinfunction "C_C") (pintype "passive"))
      (node (ref "U7") (pin "4") (pinfunction "D_4") (pintype "bidirectional"))
      (node (ref "U8") (pin "6") (pinfunction "OUTB_6") (pintype "bidirectional"))
    )
    (net (code "43") (name "Net-(U7-R)") (class "Default")
      (node (ref "JP7") (pin "2") (pinfunction "2_2") (pintype "passive"))
      (node (ref "RX3") (pin "C") (pinfunction "C_C") (pintype "passive"))
      (node (ref "U7") (pin "1") (pinfunction "R_1") (pintype "bidirectional"))
      (node (ref "U8") (pin "7") (pinfunction "INA_7") (pintype "bidirectional"))
    )
    (net (code "44") (name "Net-(U10-IN)") (class "Default")
      (node (ref "JP11") (pin "1") (pinfunction "1_1") (pintype "passive"))
      (node (ref "JP11") (pin "2") (pinfunction "2_2") (pintype "passive"))
      (node (ref "R47") (pin "2") (pinfunction "2_2") (pintype "passive"))
      (node (ref "U10") (pin "1") (pinfunction "IN_1") (pintype "bidirectional"))
      (node (ref "U11") (pin "3") (pinfunction "LOAD_3") (pintype "bidirectional"))
    )
    (net (code "45") (name "Net-(U10-LOAD)") (class "Default")
      (node (ref "JP14") (pin "1") (pinfunction "1_1") (pintype "passive"))
      (node (ref "JP14") (pin "2") (pinfunction "2_2") (pintype "passive"))
      (node (ref "R41") (pin "2") (pinfunction "2_2") (pintype "passive"))
      (node (ref "U10") (pin "3") (pinfunction "LOAD_3") (pintype "bidirectional"))
      (node (ref "U11") (pin "1") (pinfunction "IN_1") (pintype "bidirectional"))
    )
    (net (code "46") (name "Net-(U10-RA)") (class "Default")
      (node (ref "R47") (pin "1") (pinfunction "1_1") (pintype "passive"))
      (node (ref "U10") (pin "2") (pinfunction "RA_2") (pintype "bidirectional"))
    )
    (net (code "47") (name "Net-(U11-RA)") (class "Default")
      (node (ref "R41") (pin "1") (pinfunction "1_1") (pintype "passive"))
      (node (ref "U11") (pin "2") (pinfunction "RA_2") (pintype "bidirectional"))
    )
    (net (code "48") (name "Net-(U13-TRIM)") (class "Default")
      (node (ref "R25") (pin "2") (pinfunction "2_2") (pintype "passive"))
      (node (ref "R51") (pin "1") (pinfunction "1_1") (pintype "passive"))
      (node (ref "U13") (pin "5") (pinfunction "TRIM_5") (pintype "bidirectional"))
    )
    (net (code "49") (name "Net-(U17-SCL)") (class "Default")
      (node (ref "R42") (pin "1") (pinfunction "1_1") (pintype "passive"))
      (node (ref "U17") (pin "10") (pinfunction "SCL_10") (pintype "bidirectional"))
      (node (ref "U18") (pin "19") (pinfunction "SCL1_19") (pintype "bidirectional"))
    )
    (net (code "50") (name "Net-(U17-SDA)") (class "Default")
      (node (ref "R44") (pin "1") (pinfunction "1_1") (pintype "passive"))
      (node (ref "U17") (pin "9") (pinfunction "SDA_9") (pintype "bidirectional"))
      (node (ref "U18") (pin "18") (pinfunction "SDA1_18") (pintype "bidirectional"))
    )
    (net (code "51") (name "Net-(U18-VSEL)") (class "Default")
      (node (ref "R45") (pin "1") (pinfunction "1_1") (pintype "passive"))
      (node (ref "R46") (pin "2") (pinfunction "2_2") (pintype "passive"))
      (node (ref "U18") (pin "13") (pinfunction "VSEL_13") (pintype "bidirectional"))
    )
    (net (code "52") (name "SCL") (class "Default")
      (node (ref "JP3") (pin "1") (pinfunction "1_1") (pintype "passive"))
      (node (ref "U18") (pin "2") (pinfunction "SCL_2") (pintype "bidirectional"))
    )
    (net (code "53") (name "SDA") (class "Default")
      (node (ref "JP3") (pin "2") (pinfunction "2_2") (pintype "passive"))
      (node (ref "U18") (pin "3") (pinfunction "SDA_3") (pintype "bidirectional"))
    )
    (net (code "54") (name "TSAL_EN") (class "Default")
      (node (ref "JP17") (pin "2") (pinfunction "2_2") (pintype "passive"))
      (node (ref "U$11") (pin "4") (pinfunction "C_4") (pintype "bidirectional"))
    )
    (net (code "55") (name "V+") (class "Default")
      (node (ref "C25") (pin "1") (pinfunction "1_1") (pintype "passive"))
      (node (ref "C26") (pin "+") (pinfunction "+_+") (pintype "passive"))
      (node (ref "JP12") (pin "1") (pinfunction "1_1") (pintype "passive"))
      (node (ref "R28") (pin "1") (pinfunction "1_1") (pintype "passive"))
      (node (ref "R30") (pin "2") (pinfunction "2_2") (pintype "passive"))
      (node (ref "R31") (pin "2") (pinfunction "2_2") (pintype "passive"))
      (node (ref "R50") (pin "2") (pinfunction "2_2") (pintype "passive"))
      (node (ref "R51") (pin "2") (pinfunction "2_2") (pintype "passive"))
      (node (ref "U13") (pin "6") (pinfunction "VOUT+_6") (pintype "bidirectional"))
      (node (ref "U3") (pin "8") (pinfunction "VCC2_8") (pintype "bidirectional"))
      (node (ref "U7") (pin "8") (pinfunction "VCC_8") (pintype "bidirectional"))
      (node (ref "U8") (pin "8") (pinfunction "VCC2_8") (pintype "bidirectional"))
      (node (ref "V+") (pin "1") (pinfunction "1_1") (pintype "passive"))
    )
    (net (code "56") (name "V-") (class "Default")
      (node (ref "C10") (pin "C") (pinfunction "-_C") (pintype "passive"))
      (node (ref "C14") (pin "C") (pinfunction "-_C") (pintype "passive"))
      (node (ref "C17") (pin "2") (pinfunction "2_2") (pintype "passive"))
      (node (ref "C20") (pin "C") (pinfunction "-_C") (pintype "passive"))
      (node (ref "C27") (pin "2") (pinfunction "2_2") (pintype "passive"))
      (node (ref "C4") (pin "2") (pinfunction "2_2") (pintype "passive"))
      (node (ref "C5") (pin "2") (pinfunction "2_2") (pintype "passive"))
      (node (ref "C6") (pin "2") (pinfunction "2_2") (pintype "passive"))
      (node (ref "C7") (pin "2") (pinfunction "2_2") (pintype "passive"))
      (node (ref "C9") (pin "C") (pinfunction "-_C") (pintype "passive"))
      (node (ref "D1") (pin "2") (pinfunction "A_2") (pintype "passive"))
      (node (ref "IC1") (pin "4") (pinfunction "V-_4") (pintype "power_in"))
      (node (ref "JP4") (pin "1") (pinfunction "1_1") (pintype "passive"))
      (node (ref "JP4") (pin "2") (pinfunction "2_2") (pintype "passive"))
      (node (ref "JP5") (pin "2") (pinfunction "2_2") (pintype "passive"))
      (node (ref "JP9") (pin "1") (pinfunction "1_1") (pintype "passive"))
      (node (ref "JP9") (pin "2") (pinfunction "2_2") (pintype "passive"))
      (node (ref "Q1") (pin "2") (pinfunction "E_2") (pintype "passive"))
      (node (ref "R10") (pin "1") (pinfunction "1_1") (pintype "passive"))
      (node (ref "R13") (pin "1") (pinfunction "1_1") (pintype "passive"))
      (node (ref "R15") (pin "1") (pinfunction "1_1") (pintype "passive"))
      (node (ref "R35") (pin "1") (pinfunction "1_1") (pintype "passive"))
      (node (ref "R37") (pin "1") (pinfunction "1_1") (pintype "passive"))
      (node (ref "R4") (pin "1") (pinfunction "1_1") (pintype "passive"))
      (node (ref "R40") (pin "1") (pinfunction "1_1") (pintype "passive"))
      (node (ref "R46") (pin "1") (pinfunction "1_1") (pintype "passive"))
      (node (ref "R48") (pin "1") (pinfunction "1_1") (pintype "passive"))
      (node (ref "R7") (pin "1") (pinfunction "1_1") (pintype "passive"))
      (node (ref "U$11") (pin "2") (pinfunction "K_2") (pintype "bidirectional"))
      (node (ref "U10") (pin "8") (pinfunction "GND_8") (pintype "bidirectional"))
      (node (ref "U11") (pin "8") (pinfunction "GND_8") (pintype "bidirectional"))
      (node (ref "U17") (pin "1") (pinfunction "ADDR_1") (pintype "bidirectional"))
      (node (ref "U17") (pin "3") (pinfunction "GND_3") (pintype "bidirectional"))
      (node (ref "U18") (pin "11") (pinfunction "GNDISO_11") (pintype "bidirectional"))
      (node (ref "U18") (pin "14") (pinfunction "GNDISO_14") (pintype "bidirectional"))
      (node (ref "U18") (pin "16") (pinfunction "GNDISO_16") (pintype "bidirectional"))
      (node (ref "U18") (pin "20") (pinfunction "GNDISO_20") (pintype "bidirectional"))
    )
    (net (code "57") (name "unconnected-(IC1B-OUT-Pad7)") (class "Default")
      (node (ref "IC1") (pin "7") (pinfunction "OUT_7") (pintype "output"))
    )
    (net (code "58") (name "unconnected-(U3-INA-Pad7)") (class "Default")
      (node (ref "U3") (pin "7") (pinfunction "INA_7") (pintype "bidirectional"))
    )
    (net (code "59") (name "unconnected-(U3-OUTA-Pad2)") (class "Default")
      (node (ref "U3") (pin "2") (pinfunction "OUTA_2") (pintype "bidirectional"))
    )
    (net (code "60") (name "unconnected-(U13-ON{slash}OFF-Pad3)") (class "Default")
      (node (ref "U13") (pin "3") (pinfunction "ON/OFF_3") (pintype "bidirectional"))
    )
    (net (code "61") (name "unconnected-(U17-ALERT{slash}RDY-Pad2)") (class "Default")
      (node (ref "U17") (pin "2") (pinfunction "ALERT/RDY_2") (pintype "bidirectional"))
    )
    (net (code "62") (name "unconnected-(U18-PDIS-Pad8)") (class "Default")
      (node (ref "U18") (pin "8") (pinfunction "PDIS_8") (pintype "bidirectional"))
    )
  )
)
